# kachisys.net
KiCad netlist of a schematic drawn in EAGLE
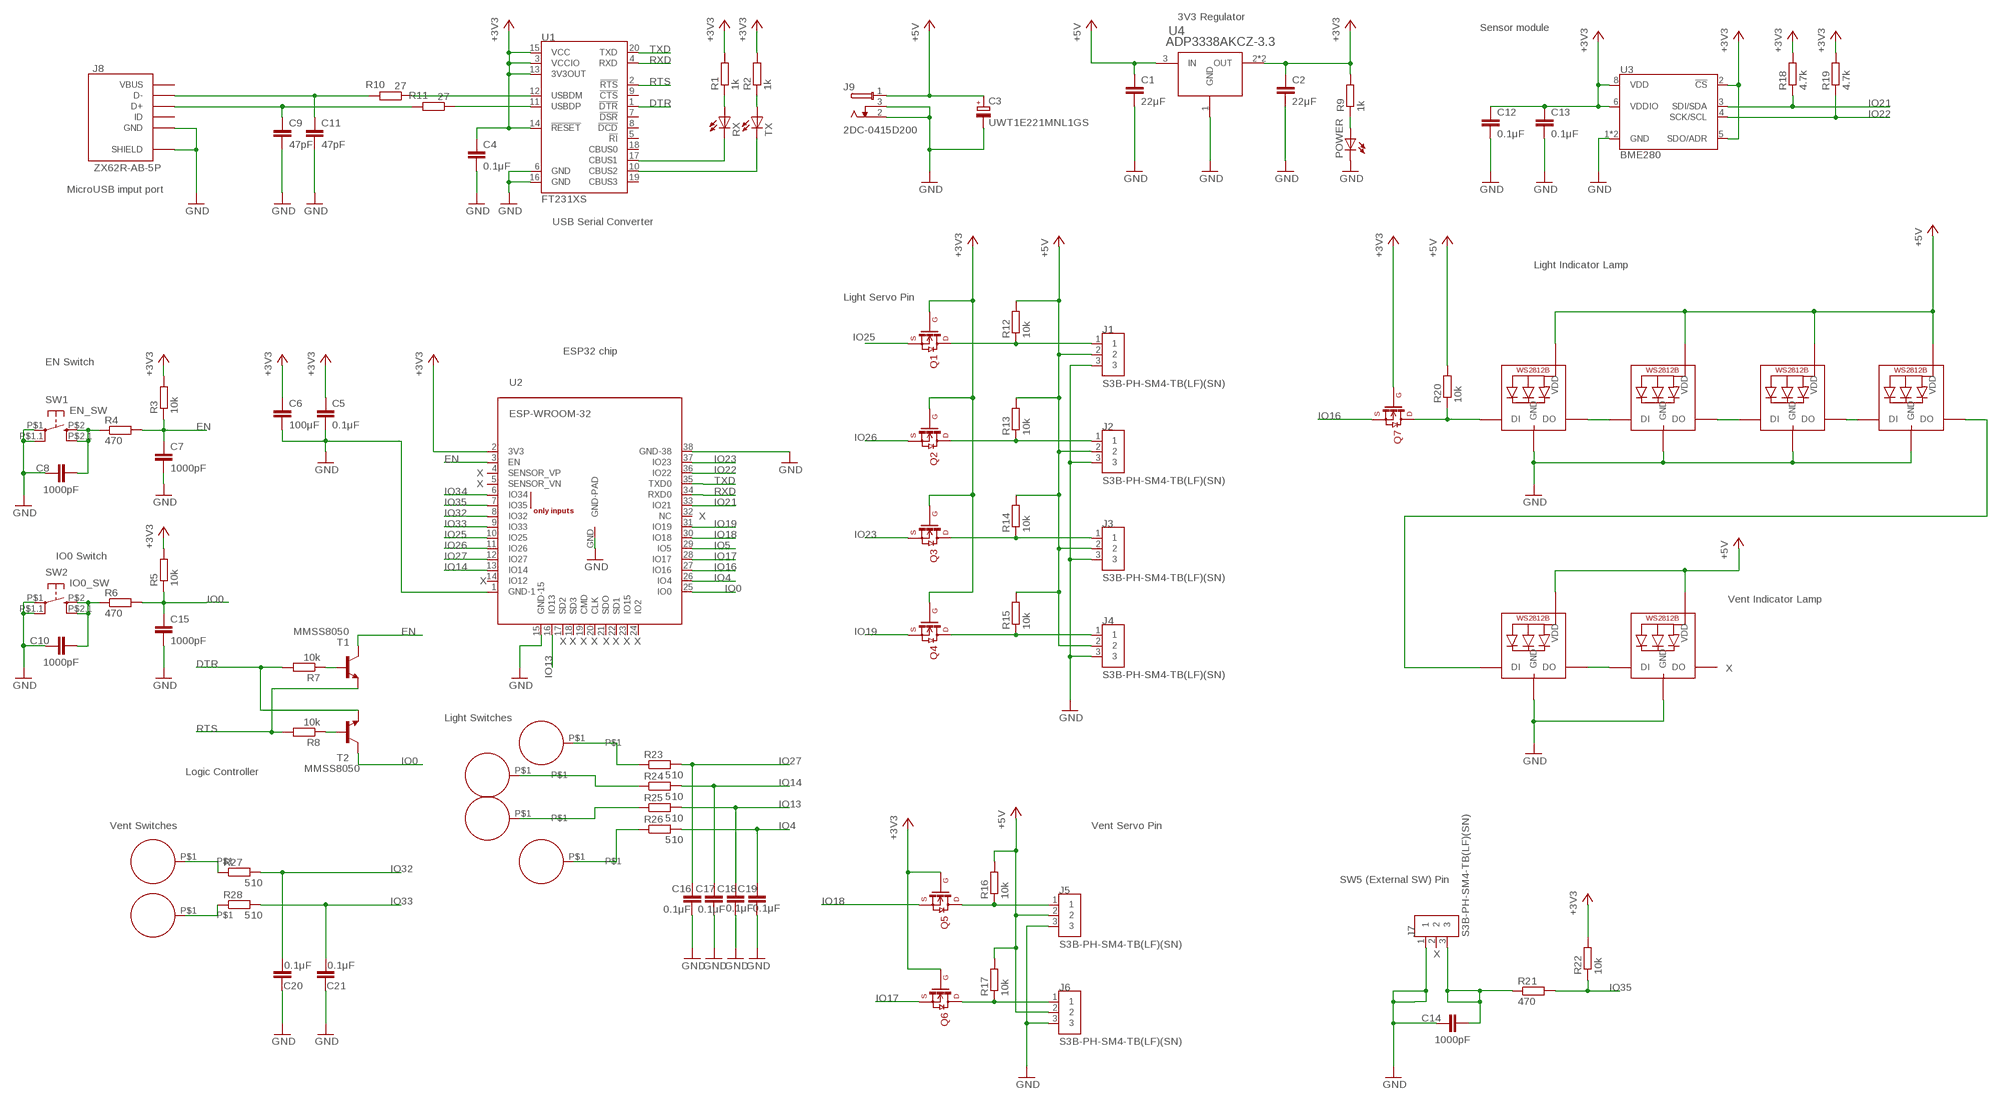
[diagram p0: schematic, sheet 1]

(export (version "E")
  (design (tool "Eeschema 10.0.6"))
  (components
    (comp (ref "C1")
      (value "22μF")
      (footprint "eagle-import:C2012")
      (libsource (lib "eagle-import") (part "resistor_348_C-EUC2012"))
    )
    (comp (ref "C2")
      (value "22μF")
      (footprint "eagle-import:C2012")
      (libsource (lib "eagle-import") (part "resistor_348_C-EUC2012"))
    )
    (comp (ref "C3")
      (value "UWT1E221MNL1GS")
      (footprint "eagle-import:NICHICON-ALMINUM-CAPACITOR-8MM")
      (libsource (lib "eagle-import") (part "UWT1E221MNL1GS"))
    )
    (comp (ref "C4")
      (value "0.1μF")
      (footprint "eagle-import:C0603")
      (libsource (lib "eagle-import") (part "resistor_348_C-EUC0603"))
    )
    (comp (ref "C5")
      (value "0.1μF")
      (footprint "eagle-import:C0603")
      (libsource (lib "eagle-import") (part "resistor_348_C-EUC0603"))
    )
    (comp (ref "C6")
      (value "100μF")
      (footprint "eagle-import:C3225")
      (libsource (lib "eagle-import") (part "resistor_348_C-EUC3225"))
    )
    (comp (ref "C7")
      (value "1000pF")
      (footprint "eagle-import:C0603")
      (libsource (lib "eagle-import") (part "resistor_348_C-EUC0603"))
    )
    (comp (ref "C8")
      (value "1000pF")
      (footprint "eagle-import:C0603")
      (libsource (lib "eagle-import") (part "resistor_348_C-EUC0603"))
    )
    (comp (ref "C9")
      (value "47pF")
      (footprint "eagle-import:C1608")
      (libsource (lib "eagle-import") (part "C-EUC1608"))
    )
    (comp (ref "C10")
      (value "1000pF")
      (footprint "eagle-import:C0603")
      (libsource (lib "eagle-import") (part "resistor_348_C-EUC0603"))
    )
    (comp (ref "C11")
      (value "47pF")
      (footprint "eagle-import:C1608")
      (libsource (lib "eagle-import") (part "C-EUC1608"))
    )
    (comp (ref "C12")
      (value "0.1μF")
      (footprint "eagle-import:C0603")
      (libsource (lib "eagle-import") (part "resistor_348_C-EUC0603"))
    )
    (comp (ref "C13")
      (value "0.1μF")
      (footprint "eagle-import:C0603")
      (libsource (lib "eagle-import") (part "resistor_348_C-EUC0603"))
    )
    (comp (ref "C14")
      (value "1000pF")
      (footprint "eagle-import:C0603")
      (libsource (lib "eagle-import") (part "resistor_348_C-EUC0603"))
    )
    (comp (ref "C15")
      (value "1000pF")
      (footprint "eagle-import:C0603")
      (libsource (lib "eagle-import") (part "resistor_348_C-EUC0603"))
    )
    (comp (ref "C16")
      (value "0.1μF")
      (footprint "eagle-import:C0603")
      (libsource (lib "eagle-import") (part "resistor_348_C-EUC0603"))
    )
    (comp (ref "C17")
      (value "0.1μF")
      (footprint "eagle-import:C0603")
      (libsource (lib "eagle-import") (part "resistor_348_C-EUC0603"))
    )
    (comp (ref "C18")
      (value "0.1μF")
      (footprint "eagle-import:C0603")
      (libsource (lib "eagle-import") (part "resistor_348_C-EUC0603"))
    )
    (comp (ref "C19")
      (value "0.1μF")
      (footprint "eagle-import:C0603")
      (libsource (lib "eagle-import") (part "resistor_348_C-EUC0603"))
    )
    (comp (ref "C20")
      (value "0.1μF")
      (footprint "eagle-import:C0603")
      (libsource (lib "eagle-import") (part "resistor_348_C-EUC0603"))
    )
    (comp (ref "C21")
      (value "0.1μF")
      (footprint "eagle-import:C0603")
      (libsource (lib "eagle-import") (part "resistor_348_C-EUC0603"))
    )
    (comp (ref "J1")
      (value "S3B-PH-SM4-TB(LF)(SN)")
      (footprint "eagle-import:JST_S3B-PH-SM4-TB(LF)(SN)")
      (fields
        (field (name "DIGI-KEY_PART_NUMBER") "455-1750-1-ND")
        (field (name "MF") "JST Sales")
        (field (name "MP") "S3B-PH-SM4-TB_LF__SN_")
      )
      (libsource (lib "eagle-import") (part "S3B-PH-SM4-TB(LF)(SN)"))
    )
    (comp (ref "J2")
      (value "S3B-PH-SM4-TB(LF)(SN)")
      (footprint "eagle-import:JST_S3B-PH-SM4-TB(LF)(SN)")
      (fields
        (field (name "DIGI-KEY_PART_NUMBER") "455-1750-1-ND")
        (field (name "MF") "JST Sales")
        (field (name "MP") "S3B-PH-SM4-TB_LF__SN_")
      )
      (libsource (lib "eagle-import") (part "S3B-PH-SM4-TB(LF)(SN)"))
    )
    (comp (ref "J3")
      (value "S3B-PH-SM4-TB(LF)(SN)")
      (footprint "eagle-import:JST_S3B-PH-SM4-TB(LF)(SN)")
      (fields
        (field (name "DIGI-KEY_PART_NUMBER") "455-1750-1-ND")
        (field (name "MF") "JST Sales")
        (field (name "MP") "S3B-PH-SM4-TB_LF__SN_")
      )
      (libsource (lib "eagle-import") (part "S3B-PH-SM4-TB(LF)(SN)"))
    )
    (comp (ref "J4")
      (value "S3B-PH-SM4-TB(LF)(SN)")
      (footprint "eagle-import:JST_S3B-PH-SM4-TB(LF)(SN)")
      (fields
        (field (name "DIGI-KEY_PART_NUMBER") "455-1750-1-ND")
        (field (name "MF") "JST Sales")
        (field (name "MP") "S3B-PH-SM4-TB_LF__SN_")
      )
      (libsource (lib "eagle-import") (part "S3B-PH-SM4-TB(LF)(SN)"))
    )
    (comp (ref "J5")
      (value "S3B-PH-SM4-TB(LF)(SN)")
      (footprint "eagle-import:JST_S3B-PH-SM4-TB(LF)(SN)")
      (fields
        (field (name "DIGI-KEY_PART_NUMBER") "455-1750-1-ND")
        (field (name "MF") "JST Sales")
        (field (name "MP") "S3B-PH-SM4-TB_LF__SN_")
      )
      (libsource (lib "eagle-import") (part "S3B-PH-SM4-TB(LF)(SN)"))
    )
    (comp (ref "J6")
      (value "S3B-PH-SM4-TB(LF)(SN)")
      (footprint "eagle-import:JST_S3B-PH-SM4-TB(LF)(SN)")
      (fields
        (field (name "DIGI-KEY_PART_NUMBER") "455-1750-1-ND")
        (field (name "MF") "JST Sales")
        (field (name "MP") "S3B-PH-SM4-TB_LF__SN_")
      )
      (libsource (lib "eagle-import") (part "S3B-PH-SM4-TB(LF)(SN)"))
    )
    (comp (ref "J7")
      (value "S3B-PH-SM4-TB(LF)(SN)")
      (footprint "eagle-import:JST_S3B-PH-SM4-TB(LF)(SN)")
      (fields
        (field (name "DIGI-KEY_PART_NUMBER") "455-1750-1-ND")
        (field (name "MF") "JST Sales")
        (field (name "MP") "S3B-PH-SM4-TB_LF__SN_")
      )
      (libsource (lib "eagle-import") (part "S3B-PH-SM4-TB(LF)(SN)"))
    )
    (comp (ref "J8")
      (value "ZX62R-AB-5P")
      (footprint "eagle-import:ZX62R-B-5PA")
      (libsource (lib "eagle-import") (part "ZX62R-AB-5P"))
    )
    (comp (ref "J9")
      (value "2DC-0415D200")
      (footprint "eagle-import:2DC-0415D200")
      (libsource (lib "eagle-import") (part "2DC-0415D200"))
    )
    (comp (ref "LED1")
      (value "WS2812B_5050N")
      (footprint "eagle-import:WS2812B-NARROW")
      (libsource (lib "eagle-import") (part "WS2812B_5050N"))
    )
    (comp (ref "LED2")
      (value "WS2812B_5050N")
      (footprint "eagle-import:WS2812B-NARROW")
      (libsource (lib "eagle-import") (part "WS2812B_5050N"))
    )
    (comp (ref "LED3")
      (value "WS2812B_5050N")
      (footprint "eagle-import:WS2812B-NARROW")
      (libsource (lib "eagle-import") (part "WS2812B_5050N"))
    )
    (comp (ref "LED4")
      (value "WS2812B_5050N")
      (footprint "eagle-import:WS2812B-NARROW")
      (libsource (lib "eagle-import") (part "WS2812B_5050N"))
    )
    (comp (ref "LED5")
      (value "WS2812B_5050N")
      (footprint "eagle-import:WS2812B-NARROW")
      (libsource (lib "eagle-import") (part "WS2812B_5050N"))
    )
    (comp (ref "LED6")
      (value "WS2812B_5050N")
      (footprint "eagle-import:WS2812B-NARROW")
      (libsource (lib "eagle-import") (part "WS2812B_5050N"))
    )
    (comp (ref "POWER")
      (value "LEDCHIP-LED0603")
      (footprint "eagle-import:CHIP-LED0603")
      (libsource (lib "eagle-import") (part "LEDCHIP-LED0603"))
    )
    (comp (ref "Q1")
      (value "BSS138")
      (footprint "eagle-import:SOT-23")
      (libsource (lib "eagle-import") (part "BSS138"))
    )
    (comp (ref "Q2")
      (value "BSS138")
      (footprint "eagle-import:SOT-23")
      (libsource (lib "eagle-import") (part "BSS138"))
    )
    (comp (ref "Q3")
      (value "BSS138")
      (footprint "eagle-import:SOT-23")
      (libsource (lib "eagle-import") (part "BSS138"))
    )
    (comp (ref "Q4")
      (value "BSS138")
      (footprint "eagle-import:SOT-23")
      (libsource (lib "eagle-import") (part "BSS138"))
    )
    (comp (ref "Q5")
      (value "BSS138")
      (footprint "eagle-import:SOT-23")
      (libsource (lib "eagle-import") (part "BSS138"))
    )
    (comp (ref "Q6")
      (value "BSS138")
      (footprint "eagle-import:SOT-23")
      (libsource (lib "eagle-import") (part "BSS138"))
    )
    (comp (ref "Q7")
      (value "BSS138")
      (footprint "eagle-import:SOT-23")
      (libsource (lib "eagle-import") (part "BSS138"))
    )
    (comp (ref "R1")
      (value "1k")
      (footprint "eagle-import:R0603")
      (libsource (lib "eagle-import") (part "R-EU_R0603"))
    )
    (comp (ref "R2")
      (value "1k")
      (footprint "eagle-import:R0603")
      (libsource (lib "eagle-import") (part "R-EU_R0603"))
    )
    (comp (ref "R3")
      (value "10k")
      (footprint "eagle-import:R0603")
      (libsource (lib "eagle-import") (part "R-EU_R0603"))
    )
    (comp (ref "R4")
      (value "470")
      (footprint "eagle-import:R0603")
      (libsource (lib "eagle-import") (part "R-EU_R0603"))
    )
    (comp (ref "R5")
      (value "10k")
      (footprint "eagle-import:R0603")
      (libsource (lib "eagle-import") (part "R-EU_R0603"))
    )
    (comp (ref "R6")
      (value "470")
      (footprint "eagle-import:R0603")
      (libsource (lib "eagle-import") (part "R-EU_R0603"))
    )
    (comp (ref "R7")
      (value "10k")
      (footprint "eagle-import:R0603")
      (libsource (lib "eagle-import") (part "R-EU_R0603"))
    )
    (comp (ref "R8")
      (value "10k")
      (footprint "eagle-import:R0603")
      (libsource (lib "eagle-import") (part "R-EU_R0603"))
    )
    (comp (ref "R9")
      (value "1k")
      (footprint "eagle-import:R0603")
      (libsource (lib "eagle-import") (part "R-EU_R0603"))
    )
    (comp (ref "R10")
      (value "27")
      (footprint "eagle-import:R0603")
      (libsource (lib "eagle-import") (part "R-EU_R0603"))
    )
    (comp (ref "R11")
      (value "27")
      (footprint "eagle-import:R0603")
      (libsource (lib "eagle-import") (part "R-EU_R0603"))
    )
    (comp (ref "R12")
      (value "10k")
      (footprint "eagle-import:R0603")
      (libsource (lib "eagle-import") (part "R-EU_R0603"))
    )
    (comp (ref "R13")
      (value "10k")
      (footprint "eagle-import:R0603")
      (libsource (lib "eagle-import") (part "R-EU_R0603"))
    )
    (comp (ref "R14")
      (value "10k")
      (footprint "eagle-import:R0603")
      (libsource (lib "eagle-import") (part "R-EU_R0603"))
    )
    (comp (ref "R15")
      (value "10k")
      (footprint "eagle-import:R0603")
      (libsource (lib "eagle-import") (part "R-EU_R0603"))
    )
    (comp (ref "R16")
      (value "10k")
      (footprint "eagle-import:R0603")
      (libsource (lib "eagle-import") (part "R-EU_R0603"))
    )
    (comp (ref "R17")
      (value "10k")
      (footprint "eagle-import:R0603")
      (libsource (lib "eagle-import") (part "R-EU_R0603"))
    )
    (comp (ref "R18")
      (value "4.7k")
      (footprint "eagle-import:R0603")
      (libsource (lib "eagle-import") (part "R-EU_R0603"))
    )
    (comp (ref "R19")
      (value "4.7k")
      (footprint "eagle-import:R0603")
      (libsource (lib "eagle-import") (part "R-EU_R0603"))
    )
    (comp (ref "R20")
      (value "10k")
      (footprint "eagle-import:R0603")
      (libsource (lib "eagle-import") (part "R-EU_R0603"))
    )
    (comp (ref "R21")
      (value "470")
      (footprint "eagle-import:R0603")
      (libsource (lib "eagle-import") (part "R-EU_R0603"))
    )
    (comp (ref "R22")
      (value "10k")
      (footprint "eagle-import:R0603")
      (libsource (lib "eagle-import") (part "R-EU_R0603"))
    )
    (comp (ref "R23")
      (value "510")
      (footprint "eagle-import:R0603")
      (libsource (lib "eagle-import") (part "R-EU_R0603"))
    )
    (comp (ref "R24")
      (value "510")
      (footprint "eagle-import:R0603")
      (libsource (lib "eagle-import") (part "R-EU_R0603"))
    )
    (comp (ref "R25")
      (value "510")
      (footprint "eagle-import:R0603")
      (libsource (lib "eagle-import") (part "R-EU_R0603"))
    )
    (comp (ref "R26")
      (value "510")
      (footprint "eagle-import:R0603")
      (libsource (lib "eagle-import") (part "R-EU_R0603"))
    )
    (comp (ref "R27")
      (value "510")
      (footprint "eagle-import:R0603")
      (libsource (lib "eagle-import") (part "R-EU_R0603"))
    )
    (comp (ref "R28")
      (value "510")
      (footprint "eagle-import:R0603")
      (libsource (lib "eagle-import") (part "R-EU_R0603"))
    )
    (comp (ref "RX")
      (value "LEDCHIP-LED0603")
      (footprint "eagle-import:CHIP-LED0603")
      (libsource (lib "eagle-import") (part "LEDCHIP-LED0603"))
    )
    (comp (ref "SW1")
      (value "EN_SW")
      (footprint "eagle-import:SKRPACE010")
      (libsource (lib "eagle-import") (part "DTS6_SMD"))
    )
    (comp (ref "SW2")
      (value "IO0_SW")
      (footprint "eagle-import:SKRPACE010")
      (libsource (lib "eagle-import") (part "DTS6_SMD"))
    )
    (comp (ref "T1")
      (value "MMSS8050")
      (footprint "eagle-import:SOT23-EBC")
      (libsource (lib "eagle-import") (part "-NPN-SOT23-EBC"))
    )
    (comp (ref "T2")
      (value "MMSS8050")
      (footprint "eagle-import:SOT23-EBC")
      (libsource (lib "eagle-import") (part "-NPN-SOT23-EBC"))
    )
    (comp (ref "TPAD1")
      (value "ESP32-TOUCHPAD")
      (footprint "eagle-import:ESP32-TOUCHPAD-10MM")
      (libsource (lib "eagle-import") (part "ESP32-TOUCHPAD"))
    )
    (comp (ref "TPAD2")
      (value "ESP32-TOUCHPAD")
      (footprint "eagle-import:ESP32-TOUCHPAD-10MM")
      (libsource (lib "eagle-import") (part "ESP32-TOUCHPAD"))
    )
    (comp (ref "TPAD3")
      (value "ESP32-TOUCHPAD")
      (footprint "eagle-import:ESP32-TOUCHPAD-10MM")
      (libsource (lib "eagle-import") (part "ESP32-TOUCHPAD"))
    )
    (comp (ref "TPAD4")
      (value "ESP32-TOUCHPAD")
      (footprint "eagle-import:ESP32-TOUCHPAD-10MM")
      (libsource (lib "eagle-import") (part "ESP32-TOUCHPAD"))
    )
    (comp (ref "TPAD5")
      (value "ESP32-TOUCHPAD")
      (footprint "eagle-import:ESP32-TOUCHPAD-10MM")
      (libsource (lib "eagle-import") (part "ESP32-TOUCHPAD"))
    )
    (comp (ref "TPAD6")
      (value "ESP32-TOUCHPAD")
      (footprint "eagle-import:ESP32-TOUCHPAD-10MM")
      (libsource (lib "eagle-import") (part "ESP32-TOUCHPAD"))
    )
    (comp (ref "TX")
      (value "LEDCHIP-LED0603")
      (footprint "eagle-import:CHIP-LED0603")
      (libsource (lib "eagle-import") (part "LEDCHIP-LED0603"))
    )
    (comp (ref "U1")
      (value "FT231XS")
      (footprint "eagle-import:SSOP20_L")
      (libsource (lib "eagle-import") (part "FT231XS"))
    )
    (comp (ref "U2")
      (value "ESP-WROOM-32")
      (footprint "eagle-import:ESP-WROOM-32")
      (libsource (lib "eagle-import") (part "ESP-WROOM-32"))
    )
    (comp (ref "U3")
      (value "BME280")
      (footprint "eagle-import:LGA-8-2.5X2.5")
      (libsource (lib "eagle-import") (part "BME280"))
    )
    (comp (ref "U4")
      (value "ADP3338AKCZ-3.3")
      (footprint "eagle-import:SOT233")
      (libsource (lib "eagle-import") (part "ADP3338AKCZ-3.3"))
    )
  )
  (nets
    (net (code "1") (name "+3V3") (class "Default")
      (node (ref "C12") (pin "1") (pinfunction "1_1") (pintype "passive"))
      (node (ref "C13") (pin "1") (pinfunction "1_1") (pintype "passive"))
      (node (ref "C2") (pin "1") (pinfunction "1_1") (pintype "passive"))
      (node (ref "C4") (pin "1") (pinfunction "1_1") (pintype "passive"))
      (node (ref "C5") (pin "1") (pinfunction "1_1") (pintype "passive"))
      (node (ref "C6") (pin "1") (pinfunction "1_1") (pintype "passive"))
      (node (ref "Q1") (pin "G") (pinfunction "G_G") (pintype "passive"))
      (node (ref "Q2") (pin "G") (pinfunction "G_G") (pintype "passive"))
      (node (ref "Q3") (pin "G") (pinfunction "G_G") (pintype "passive"))
      (node (ref "Q4") (pin "G") (pinfunction "G_G") (pintype "passive"))
      (node (ref "Q5") (pin "G") (pinfunction "G_G") (pintype "passive"))
      (node (ref "Q6") (pin "G") (pinfunction "G_G") (pintype "passive"))
      (node (ref "Q7") (pin "G") (pinfunction "G_G") (pintype "passive"))
      (node (ref "R1") (pin "2") (pinfunction "2_2") (pintype "passive"))
      (node (ref "R18") (pin "2") (pinfunction "2_2") (pintype "passive"))
      (node (ref "R19") (pin "2") (pinfunction "2_2") (pintype "passive"))
      (node (ref "R2") (pin "2") (pinfunction "2_2") (pintype "passive"))
      (node (ref "R22") (pin "2") (pinfunction "2_2") (pintype "passive"))
      (node (ref "R3") (pin "2") (pinfunction "2_2") (pintype "passive"))
      (node (ref "R5") (pin "2") (pinfunction "2_2") (pintype "passive"))
      (node (ref "R9") (pin "2") (pinfunction "2_2") (pintype "passive"))
      (node (ref "U1") (pin "13") (pinfunction "3V3OUT_13") (pintype "bidirectional"))
      (node (ref "U1") (pin "14") (pinfunction "~{RESET}_14") (pintype "bidirectional"))
      (node (ref "U1") (pin "15") (pinfunction "VCC_15") (pintype "bidirectional"))
      (node (ref "U1") (pin "3") (pinfunction "VCCIO_3") (pintype "bidirectional"))
      (node (ref "U2") (pin "2") (pinfunction "3V3_2") (pintype "bidirectional"))
      (node (ref "U3") (pin "2") (pinfunction "~{CS}_2") (pintype "bidirectional"))
      (node (ref "U3") (pin "5") (pinfunction "SDO/ADR_5") (pintype "bidirectional"))
      (node (ref "U3") (pin "6") (pinfunction "VDDIO_6") (pintype "bidirectional"))
      (node (ref "U3") (pin "8") (pinfunction "VDD_8") (pintype "bidirectional"))
      (node (ref "U4") (pin "2") (pinfunction "OUT_2") (pintype "passive"))
      (node (ref "U4") (pin "4") (pinfunction "OUT_4") (pintype "passive"))
    )
    (net (code "2") (name "+5V") (class "Default")
      (node (ref "C1") (pin "1") (pinfunction "1_1") (pintype "passive"))
      (node (ref "C3") (pin "POS") (pinfunction "+_POS") (pintype "passive"))
      (node (ref "J1") (pin "2") (pinfunction "2_2") (pintype "passive"))
      (node (ref "J2") (pin "2") (pinfunction "2_2") (pintype "passive"))
      (node (ref "J3") (pin "2") (pinfunction "2_2") (pintype "passive"))
      (node (ref "J4") (pin "2") (pinfunction "2_2") (pintype "passive"))
      (node (ref "J5") (pin "2") (pinfunction "2_2") (pintype "passive"))
      (node (ref "J6") (pin "2") (pinfunction "2_2") (pintype "passive"))
      (node (ref "J9") (pin "1") (pinfunction "1_1") (pintype "passive"))
      (node (ref "LED1") (pin "1-VDD") (pinfunction "VDD_1-VDD") (pintype "power_in"))
      (node (ref "LED2") (pin "1-VDD") (pinfunction "VDD_1-VDD") (pintype "power_in"))
      (node (ref "LED3") (pin "1-VDD") (pinfunction "VDD_1-VDD") (pintype "power_in"))
      (node (ref "LED4") (pin "1-VDD") (pinfunction "VDD_1-VDD") (pintype "power_in"))
      (node (ref "LED5") (pin "1-VDD") (pinfunction "VDD_1-VDD") (pintype "power_in"))
      (node (ref "LED6") (pin "1-VDD") (pinfunction "VDD_1-VDD") (pintype "power_in"))
      (node (ref "R12") (pin "2") (pinfunction "2_2") (pintype "passive"))
      (node (ref "R13") (pin "2") (pinfunction "2_2") (pintype "passive"))
      (node (ref "R14") (pin "2") (pinfunction "2_2") (pintype "passive"))
      (node (ref "R15") (pin "2") (pinfunction "2_2") (pintype "passive"))
      (node (ref "R16") (pin "2") (pinfunction "2_2") (pintype "passive"))
      (node (ref "R17") (pin "2") (pinfunction "2_2") (pintype "passive"))
      (node (ref "R20") (pin "2") (pinfunction "2_2") (pintype "passive"))
      (node (ref "U4") (pin "3") (pinfunction "IN_3") (pintype "passive"))
    )
    (net (code "3") (name "/DTR") (class "Default")
      (node (ref "R7") (pin "2") (pinfunction "2_2") (pintype "passive"))
      (node (ref "T2") (pin "E") (pinfunction "E_E") (pintype "passive"))
      (node (ref "U1") (pin "1") (pinfunction "~{DTR}_1") (pintype "bidirectional"))
    )
    (net (code "4") (name "/EN") (class "Default")
      (node (ref "C7") (pin "1") (pinfunction "1_1") (pintype "passive"))
      (node (ref "R3") (pin "1") (pinfunction "1_1") (pintype "passive"))
      (node (ref "R4") (pin "2") (pinfunction "2_2") (pintype "passive"))
      (node (ref "T1") (pin "C") (pinfunction "C_C") (pintype "passive"))
      (node (ref "U2") (pin "3") (pinfunction "EN_3") (pintype "bidirectional"))
    )
    (net (code "5") (name "/IO0") (class "Default")
      (node (ref "C15") (pin "1") (pinfunction "1_1") (pintype "passive"))
      (node (ref "R5") (pin "1") (pinfunction "1_1") (pintype "passive"))
      (node (ref "R6") (pin "2") (pinfunction "2_2") (pintype "passive"))
      (node (ref "T2") (pin "C") (pinfunction "C_C") (pintype "passive"))
      (node (ref "U2") (pin "25") (pinfunction "IO0_25") (pintype "bidirectional"))
    )
    (net (code "6") (name "/IO4") (class "Default")
      (node (ref "C19") (pin "1") (pinfunction "1_1") (pintype "passive"))
      (node (ref "R26") (pin "2") (pinfunction "2_2") (pintype "passive"))
      (node (ref "U2") (pin "26") (pinfunction "IO4_26") (pintype "bidirectional"))
    )
    (net (code "7") (name "/IO5") (class "Default")
      (node (ref "U2") (pin "29") (pinfunction "IO5_29") (pintype "bidirectional"))
    )
    (net (code "8") (name "/IO13") (class "Default")
      (node (ref "C18") (pin "1") (pinfunction "1_1") (pintype "passive"))
      (node (ref "R25") (pin "2") (pinfunction "2_2") (pintype "passive"))
      (node (ref "U2") (pin "16") (pinfunction "IO13_16") (pintype "bidirectional"))
    )
    (net (code "9") (name "/IO14") (class "Default")
      (node (ref "C17") (pin "1") (pinfunction "1_1") (pintype "passive"))
      (node (ref "R24") (pin "2") (pinfunction "2_2") (pintype "passive"))
      (node (ref "U2") (pin "13") (pinfunction "IO14_13") (pintype "bidirectional"))
    )
    (net (code "10") (name "/IO16") (class "Default")
      (node (ref "Q7") (pin "S") (pinfunction "S_S") (pintype "passive"))
      (node (ref "U2") (pin "27") (pinfunction "IO16_27") (pintype "bidirectional"))
    )
    (net (code "11") (name "/IO17") (class "Default")
      (node (ref "Q6") (pin "S") (pinfunction "S_S") (pintype "passive"))
      (node (ref "U2") (pin "28") (pinfunction "IO17_28") (pintype "bidirectional"))
    )
    (net (code "12") (name "/IO18") (class "Default")
      (node (ref "Q5") (pin "S") (pinfunction "S_S") (pintype "passive"))
      (node (ref "U2") (pin "30") (pinfunction "IO18_30") (pintype "bidirectional"))
    )
    (net (code "13") (name "/IO19") (class "Default")
      (node (ref "Q4") (pin "S") (pinfunction "S_S") (pintype "passive"))
      (node (ref "U2") (pin "31") (pinfunction "IO19_31") (pintype "bidirectional"))
    )
    (net (code "14") (name "/IO21") (class "Default")
      (node (ref "R18") (pin "1") (pinfunction "1_1") (pintype "passive"))
      (node (ref "U2") (pin "33") (pinfunction "IO21_33") (pintype "bidirectional"))
      (node (ref "U3") (pin "3") (pinfunction "SDI/SDA_3") (pintype "bidirectional"))
    )
    (net (code "15") (name "/IO22") (class "Default")
      (node (ref "R19") (pin "1") (pinfunction "1_1") (pintype "passive"))
      (node (ref "U2") (pin "36") (pinfunction "IO22_36") (pintype "bidirectional"))
      (node (ref "U3") (pin "4") (pinfunction "SCK/SCL_4") (pintype "bidirectional"))
    )
    (net (code "16") (name "/IO23") (class "Default")
      (node (ref "Q3") (pin "S") (pinfunction "S_S") (pintype "passive"))
      (node (ref "U2") (pin "37") (pinfunction "IO23_37") (pintype "bidirectional"))
    )
    (net (code "17") (name "/IO25") (class "Default")
      (node (ref "Q1") (pin "S") (pinfunction "S_S") (pintype "passive"))
      (node (ref "U2") (pin "10") (pinfunction "IO25_10") (pintype "bidirectional"))
    )
    (net (code "18") (name "/IO26") (class "Default")
      (node (ref "Q2") (pin "S") (pinfunction "S_S") (pintype "passive"))
      (node (ref "U2") (pin "11") (pinfunction "IO26_11") (pintype "bidirectional"))
    )
    (net (code "19") (name "/IO27") (class "Default")
      (node (ref "C16") (pin "1") (pinfunction "1_1") (pintype "passive"))
      (node (ref "R23") (pin "2") (pinfunction "2_2") (pintype "passive"))
      (node (ref "U2") (pin "12") (pinfunction "IO27_12") (pintype "bidirectional"))
    )
    (net (code "20") (name "/IO32") (class "Default")
      (node (ref "C20") (pin "2") (pinfunction "2_2") (pintype "passive"))
      (node (ref "R27") (pin "2") (pinfunction "2_2") (pintype "passive"))
      (node (ref "U2") (pin "8") (pinfunction "IO32_8") (pintype "bidirectional"))
    )
    (net (code "21") (name "/IO33") (class "Default")
      (node (ref "C21") (pin "2") (pinfunction "2_2") (pintype "passive"))
      (node (ref "R28") (pin "2") (pinfunction "2_2") (pintype "passive"))
      (node (ref "U2") (pin "9") (pinfunction "IO33_9") (pintype "bidirectional"))
    )
    (net (code "22") (name "/IO34") (class "Default")
      (node (ref "U2") (pin "6") (pinfunction "IO34_6") (pintype "input"))
    )
    (net (code "23") (name "/IO35") (class "Default")
      (node (ref "R21") (pin "2") (pinfunction "2_2") (pintype "passive"))
      (node (ref "R22") (pin "1") (pinfunction "1_1") (pintype "passive"))
      (node (ref "U2") (pin "7") (pinfunction "IO35_7") (pintype "input"))
    )
    (net (code "24") (name "/RTS") (class "Default")
      (node (ref "R8") (pin "2") (pinfunction "2_2") (pintype "passive"))
      (node (ref "T1") (pin "E") (pinfunction "E_E") (pintype "passive"))
      (node (ref "U1") (pin "2") (pinfunction "~{RTS}_2") (pintype "bidirectional"))
    )
    (net (code "25") (name "/RXD") (class "Default")
      (node (ref "U1") (pin "4") (pinfunction "RXD_4") (pintype "bidirectional"))
      (node (ref "U2") (pin "34") (pinfunction "RXD0_34") (pintype "bidirectional"))
    )
    (net (code "26") (name "/TXD") (class "Default")
      (node (ref "U1") (pin "20") (pinfunction "TXD_20") (pintype "bidirectional"))
      (node (ref "U2") (pin "35") (pinfunction "TXD0_35") (pintype "bidirectional"))
    )
    (net (code "27") (name "GND") (class "Default")
      (node (ref "C1") (pin "2") (pinfunction "2_2") (pintype "passive"))
      (node (ref "C10") (pin "1") (pinfunction "1_1") (pintype "passive"))
      (node (ref "C11") (pin "2") (pinfunction "2_2") (pintype "passive"))
      (node (ref "C12") (pin "2") (pinfunction "2_2") (pintype "passive"))
      (node (ref "C13") (pin "2") (pinfunction "2_2") (pintype "passive"))
      (node (ref "C14") (pin "1") (pinfunction "1_1") (pintype "passive"))
      (node (ref "C15") (pin "2") (pinfunction "2_2") (pintype "passive"))
      (node (ref "C16") (pin "2") (pinfunction "2_2") (pintype "passive"))
      (node (ref "C17") (pin "2") (pinfunction "2_2") (pintype "passive"))
      (node (ref "C18") (pin "2") (pinfunction "2_2") (pintype "passive"))
      (node (ref "C19") (pin "2") (pinfunction "2_2") (pintype "passive"))
      (node (ref "C2") (pin "2") (pinfunction "2_2") (pintype "passive"))
      (node (ref "C20") (pin "1") (pinfunction "1_1") (pintype "passive"))
      (node (ref "C21") (pin "1") (pinfunction "1_1") (pintype "passive"))
      (node (ref "C3") (pin "NEG") (pinfunction "-_NEG") (pintype "passive"))
      (node (ref "C4") (pin "2") (pinfunction "2_2") (pintype "passive"))
      (node (ref "C5") (pin "2") (pinfunction "2_2") (pintype "passive"))
      (node (ref "C6") (pin "2") (pinfunction "2_2") (pintype "passive"))
      (node (ref "C7") (pin "2") (pinfunction "2_2") (pintype "passive"))
      (node (ref "C8") (pin "1") (pinfunction "1_1") (pintype "passive"))
      (node (ref "C9") (pin "2") (pinfunction "2_2") (pintype "passive"))
      (node (ref "J1") (pin "3") (pinfunction "3_3") (pintype "passive"))
      (node (ref "J2") (pin "3") (pinfunction "3_3") (pintype "passive"))
      (node (ref "J3") (pin "3") (pinfunction "3_3") (pintype "passive"))
      (node (ref "J4") (pin "3") (pinfunction "3_3") (pintype "passive"))
      (node (ref "J5") (pin "3") (pinfunction "3_3") (pintype "passive"))
      (node (ref "J6") (pin "3") (pinfunction "3_3") (pintype "passive"))
      (node (ref "J7") (pin "1") (pinfunction "1_1") (pintype "passive"))
      (node (ref "J8") (pin "GND") (pinfunction "GND_GND") (pintype "bidirectional"))
      (node (ref "J8") (pin "SHIELD@1") (pinfunction "SHIELD_SHIELD@1") (pintype "bidirectional"))
      (node (ref "J8") (pin "SHIELD@2") (pinfunction "SHIELD_SHIELD@2") (pintype "bidirectional"))
      (node (ref "J8") (pin "SHIELD@3") (pinfunction "SHIELD_SHIELD@3") (pintype "bidirectional"))
      (node (ref "J8") (pin "SHIELD@4") (pinfunction "SHIELD_SHIELD@4") (pintype "bidirectional"))
      (node (ref "J9") (pin "2") (pinfunction "2_2") (pintype "passive"))
      (node (ref "J9") (pin "3") (pinfunction "3_3") (pintype "passive"))
      (node (ref "LED1") (pin "3-GND") (pinfunction "GND_3-GND") (pintype "power_in"))
      (node (ref "LED2") (pin "3-GND") (pinfunction "GND_3-GND") (pintype "power_in"))
      (node (ref "LED3") (pin "3-GND") (pinfunction "GND_3-GND") (pintype "power_in"))
      (node (ref "LED4") (pin "3-GND") (pinfunction "GND_3-GND") (pintype "power_in"))
      (node (ref "LED5") (pin "3-GND") (pinfunction "GND_3-GND") (pintype "power_in"))
      (node (ref "LED6") (pin "3-GND") (pinfunction "GND_3-GND") (pintype "power_in"))
      (node (ref "POWER") (pin "C") (pinfunction "C_C") (pintype "passive"))
      (node (ref "SW1") (pin "P$1") (pinfunction "P_P$1") (pintype "passive"))
      (node (ref "SW1") (pin "P$1.1") (pinfunction "P1_P$1.1") (pintype "passive"))
      (node (ref "SW2") (pin "P$1") (pinfunction "P_P$1") (pintype "passive"))
      (node (ref "SW2") (pin "P$1.1") (pinfunction "P1_P$1.1") (pintype "passive"))
      (node (ref "U1") (pin "16") (pinfunction "GND_16") (pintype "bidirectional"))
      (node (ref "U1") (pin "6") (pinfunction "GND_6") (pintype "bidirectional"))
      (node (ref "U2") (pin "1") (pinfunction "GND-1_1") (pintype "bidirectional"))
      (node (ref "U2") (pin "15") (pinfunction "GND-15_15") (pintype "bidirectional"))
      (node (ref "U2") (pin "38") (pinfunction "GND-38_38") (pintype "bidirectional"))
      (node (ref "U2") (pin "GND") (pinfunction "GND-PAD_GND") (pintype "bidirectional"))
      (node (ref "U3") (pin "1") (pinfunction "GND_1") (pintype "bidirectional"))
      (node (ref "U3") (pin "7") (pinfunction "GND_7") (pintype "bidirectional"))
      (node (ref "U4") (pin "1") (pinfunction "GND_1") (pintype "passive"))
    )
    (net (code "28") (name "Net-(C9-Pad1)") (class "Default")
      (node (ref "C9") (pin "1") (pinfunction "1_1") (pintype "passive"))
      (node (ref "J8") (pin "D+") (pinfunction "D+_D+") (pintype "bidirectional"))
      (node (ref "R11") (pin "2") (pinfunction "2_2") (pintype "passive"))
    )
    (net (code "29") (name "Net-(C11-Pad1)") (class "Default")
      (node (ref "C11") (pin "1") (pinfunction "1_1") (pintype "passive"))
      (node (ref "J8") (pin "D-") (pinfunction "D-_D-") (pintype "bidirectional"))
      (node (ref "R10") (pin "2") (pinfunction "2_2") (pintype "passive"))
    )
    (net (code "30") (name "Net-(C14-Pad2)") (class "Default")
      (node (ref "C14") (pin "2") (pinfunction "2_2") (pintype "passive"))
      (node (ref "J7") (pin "3") (pinfunction "3_3") (pintype "passive"))
      (node (ref "R21") (pin "1") (pinfunction "1_1") (pintype "passive"))
    )
    (net (code "31") (name "Net-(J1-Pad1)") (class "Default")
      (node (ref "J1") (pin "1") (pinfunction "1_1") (pintype "passive"))
      (node (ref "Q1") (pin "D") (pinfunction "D_D") (pintype "passive"))
      (node (ref "R12") (pin "1") (pinfunction "1_1") (pintype "passive"))
    )
    (net (code "32") (name "Net-(J2-Pad1)") (class "Default")
      (node (ref "J2") (pin "1") (pinfunction "1_1") (pintype "passive"))
      (node (ref "Q2") (pin "D") (pinfunction "D_D") (pintype "passive"))
      (node (ref "R13") (pin "1") (pinfunction "1_1") (pintype "passive"))
    )
    (net (code "33") (name "Net-(J3-Pad1)") (class "Default")
      (node (ref "J3") (pin "1") (pinfunction "1_1") (pintype "passive"))
      (node (ref "Q3") (pin "D") (pinfunction "D_D") (pintype "passive"))
      (node (ref "R14") (pin "1") (pinfunction "1_1") (pintype "passive"))
    )
    (net (code "34") (name "Net-(J4-Pad1)") (class "Default")
      (node (ref "J4") (pin "1") (pinfunction "1_1") (pintype "passive"))
      (node (ref "Q4") (pin "D") (pinfunction "D_D") (pintype "passive"))
      (node (ref "R15") (pin "1") (pinfunction "1_1") (pintype "passive"))
    )
    (net (code "35") (name "Net-(J5-Pad1)") (class "Default")
      (node (ref "J5") (pin "1") (pinfunction "1_1") (pintype "passive"))
      (node (ref "Q5") (pin "D") (pinfunction "D_D") (pintype "passive"))
      (node (ref "R16") (pin "1") (pinfunction "1_1") (pintype "passive"))
    )
    (net (code "36") (name "Net-(J6-Pad1)") (class "Default")
      (node (ref "J6") (pin "1") (pinfunction "1_1") (pintype "passive"))
      (node (ref "Q6") (pin "D") (pinfunction "D_D") (pintype "passive"))
      (node (ref "R17") (pin "1") (pinfunction "1_1") (pintype "passive"))
    )
    (net (code "37") (name "Net-(LED1-DI)") (class "Default")
      (node (ref "LED1") (pin "4-DIN") (pinfunction "DI_4-DIN") (pintype "input"))
      (node (ref "Q7") (pin "D") (pinfunction "D_D") (pintype "passive"))
      (node (ref "R20") (pin "1") (pinfunction "1_1") (pintype "passive"))
    )
    (net (code "38") (name "Net-(LED1-DO)") (class "Default")
      (node (ref "LED1") (pin "2-DOUT") (pinfunction "DO_2-DOUT") (pintype "output"))
      (node (ref "LED2") (pin "4-DIN") (pinfunction "DI_4-DIN") (pintype "input"))
    )
    (net (code "39") (name "Net-(LED2-DO)") (class "Default")
      (node (ref "LED2") (pin "2-DOUT") (pinfunction "DO_2-DOUT") (pintype "output"))
      (node (ref "LED3") (pin "4-DIN") (pinfunction "DI_4-DIN") (pintype "input"))
    )
    (net (code "40") (name "Net-(LED3-DO)") (class "Default")
      (node (ref "LED3") (pin "2-DOUT") (pinfunction "DO_2-DOUT") (pintype "output"))
      (node (ref "LED4") (pin "4-DIN") (pinfunction "DI_4-DIN") (pintype "input"))
    )
    (net (code "41") (name "Net-(LED4-DO)") (class "Default")
      (node (ref "LED4") (pin "2-DOUT") (pinfunction "DO_2-DOUT") (pintype "output"))
      (node (ref "LED5") (pin "4-DIN") (pinfunction "DI_4-DIN") (pintype "input"))
    )
    (net (code "42") (name "Net-(LED5-DO)") (class "Default")
      (node (ref "LED5") (pin "2-DOUT") (pinfunction "DO_2-DOUT") (pintype "output"))
      (node (ref "LED6") (pin "4-DIN") (pinfunction "DI_4-DIN") (pintype "input"))
    )
    (net (code "43") (name "Net-(POWER-PadA)") (class "Default")
      (node (ref "POWER") (pin "A") (pinfunction "A_A") (pintype "passive"))
      (node (ref "R9") (pin "1") (pinfunction "1_1") (pintype "passive"))
    )
    (net (code "44") (name "Net-(R1-Pad1)") (class "Default")
      (node (ref "R1") (pin "1") (pinfunction "1_1") (pintype "passive"))
      (node (ref "RX") (pin "A") (pinfunction "A_A") (pintype "passive"))
    )
    (net (code "45") (name "Net-(R2-Pad1)") (class "Default")
      (node (ref "R2") (pin "1") (pinfunction "1_1") (pintype "passive"))
      (node (ref "TX") (pin "A") (pinfunction "A_A") (pintype "passive"))
    )
    (net (code "46") (name "Net-(R7-Pad1)") (class "Default")
      (node (ref "R7") (pin "1") (pinfunction "1_1") (pintype "passive"))
      (node (ref "T1") (pin "B") (pinfunction "B_B") (pintype "passive"))
    )
    (net (code "47") (name "Net-(R8-Pad1)") (class "Default")
      (node (ref "R8") (pin "1") (pinfunction "1_1") (pintype "passive"))
      (node (ref "T2") (pin "B") (pinfunction "B_B") (pintype "passive"))
    )
    (net (code "48") (name "Net-(R23-Pad1)") (class "Default")
      (node (ref "R23") (pin "1") (pinfunction "1_1") (pintype "passive"))
      (node (ref "TPAD1") (pin "P$1") (pinfunction "P$1_P$1") (pintype "bidirectional"))
    )
    (net (code "49") (name "Net-(R24-Pad1)") (class "Default")
      (node (ref "R24") (pin "1") (pinfunction "1_1") (pintype "passive"))
      (node (ref "TPAD2") (pin "P$1") (pinfunction "P$1_P$1") (pintype "bidirectional"))
    )
    (net (code "50") (name "Net-(R25-Pad1)") (class "Default")
      (node (ref "R25") (pin "1") (pinfunction "1_1") (pintype "passive"))
      (node (ref "TPAD3") (pin "P$1") (pinfunction "P$1_P$1") (pintype "bidirectional"))
    )
    (net (code "51") (name "Net-(R26-Pad1)") (class "Default")
      (node (ref "R26") (pin "1") (pinfunction "1_1") (pintype "passive"))
      (node (ref "TPAD4") (pin "P$1") (pinfunction "P$1_P$1") (pintype "bidirectional"))
    )
    (net (code "52") (name "Net-(R27-Pad1)") (class "Default")
      (node (ref "R27") (pin "1") (pinfunction "1_1") (pintype "passive"))
      (node (ref "TPAD5") (pin "P$1") (pinfunction "P$1_P$1") (pintype "bidirectional"))
    )
    (net (code "53") (name "Net-(R28-Pad1)") (class "Default")
      (node (ref "R28") (pin "1") (pinfunction "1_1") (pintype "passive"))
      (node (ref "TPAD6") (pin "P$1") (pinfunction "P$1_P$1") (pintype "bidirectional"))
    )
    (net (code "54") (name "Net-(SW1-S)") (class "Default")
      (node (ref "C8") (pin "2") (pinfunction "2_2") (pintype "passive"))
      (node (ref "R4") (pin "1") (pinfunction "1_1") (pintype "passive"))
      (node (ref "SW1") (pin "P$2") (pinfunction "S_P$2") (pintype "passive"))
      (node (ref "SW1") (pin "P$2.1") (pinfunction "S1_P$2.1") (pintype "passive"))
    )
    (net (code "55") (name "Net-(SW2-S)") (class "Default")
      (node (ref "C10") (pin "2") (pinfunction "2_2") (pintype "passive"))
      (node (ref "R6") (pin "1") (pinfunction "1_1") (pintype "passive"))
      (node (ref "SW2") (pin "P$2") (pinfunction "S_P$2") (pintype "passive"))
      (node (ref "SW2") (pin "P$2.1") (pinfunction "S1_P$2.1") (pintype "passive"))
    )
    (net (code "56") (name "Net-(U1-CBUS1)") (class "Default")
      (node (ref "RX") (pin "C") (pinfunction "C_C") (pintype "passive"))
      (node (ref "U1") (pin "17") (pinfunction "CBUS1_17") (pintype "bidirectional"))
    )
    (net (code "57") (name "Net-(U1-CBUS2)") (class "Default")
      (node (ref "TX") (pin "C") (pinfunction "C_C") (pintype "passive"))
      (node (ref "U1") (pin "10") (pinfunction "CBUS2_10") (pintype "bidirectional"))
    )
    (net (code "58") (name "Net-(U1-USBDM)") (class "Default")
      (node (ref "R10") (pin "1") (pinfunction "1_1") (pintype "passive"))
      (node (ref "U1") (pin "12") (pinfunction "USBDM_12") (pintype "bidirectional"))
    )
    (net (code "59") (name "Net-(U1-USBDP)") (class "Default")
      (node (ref "R11") (pin "1") (pinfunction "1_1") (pintype "passive"))
      (node (ref "U1") (pin "11") (pinfunction "USBDP_11") (pintype "bidirectional"))
    )
    (net (code "60") (name "unconnected-(J7-Pad2)") (class "Default")
      (node (ref "J7") (pin "2") (pinfunction "2_2") (pintype "passive"))
    )
    (net (code "61") (name "unconnected-(J8-PadID)") (class "Default")
      (node (ref "J8") (pin "ID") (pinfunction "ID_ID") (pintype "bidirectional"))
    )
    (net (code "62") (name "unconnected-(J8-VBUS-PadVCC)") (class "Default")
      (node (ref "J8") (pin "VCC") (pinfunction "VBUS_VCC") (pintype "bidirectional"))
    )
    (net (code "63") (name "unconnected-(LED6-DO-Pad2-DOUT)") (class "Default")
      (node (ref "LED6") (pin "2-DOUT") (pinfunction "DO_2-DOUT") (pintype "output"))
    )
    (net (code "64") (name "unconnected-(U1-CBUS0-Pad18)") (class "Default")
      (node (ref "U1") (pin "18") (pinfunction "CBUS0_18") (pintype "bidirectional"))
    )
    (net (code "65") (name "unconnected-(U1-CBUS3-Pad19)") (class "Default")
      (node (ref "U1") (pin "19") (pinfunction "CBUS3_19") (pintype "bidirectional"))
    )
    (net (code "66") (name "unconnected-(U1-~{CTS}-Pad9)") (class "Default")
      (node (ref "U1") (pin "9") (pinfunction "~{CTS}_9") (pintype "bidirectional"))
    )
    (net (code "67") (name "unconnected-(U1-~{DCD}-Pad8)") (class "Default")
      (node (ref "U1") (pin "8") (pinfunction "~{DCD}_8") (pintype "bidirectional"))
    )
    (net (code "68") (name "unconnected-(U1-~{DSR}-Pad7)") (class "Default")
      (node (ref "U1") (pin "7") (pinfunction "~{DSR}_7") (pintype "bidirectional"))
    )
    (net (code "69") (name "unconnected-(U1-~{RI}-Pad5)") (class "Default")
      (node (ref "U1") (pin "5") (pinfunction "~{RI}_5") (pintype "bidirectional"))
    )
    (net (code "70") (name "unconnected-(U2-CLK-Pad20)") (class "Default")
      (node (ref "U2") (pin "20") (pinfunction "CLK_20") (pintype "bidirectional"))
    )
    (net (code "71") (name "unconnected-(U2-CMD-Pad19)") (class "Default")
      (node (ref "U2") (pin "19") (pinfunction "CMD_19") (pintype "bidirectional"))
    )
    (net (code "72") (name "unconnected-(U2-IO2-Pad24)") (class "Default")
      (node (ref "U2") (pin "24") (pinfunction "IO2_24") (pintype "bidirectional"))
    )
    (net (code "73") (name "unconnected-(U2-IO12-Pad14)") (class "Default")
      (node (ref "U2") (pin "14") (pinfunction "IO12_14") (pintype "bidirectional"))
    )
    (net (code "74") (name "unconnected-(U2-IO15-Pad23)") (class "Default")
      (node (ref "U2") (pin "23") (pinfunction "IO15_23") (pintype "bidirectional"))
    )
    (net (code "75") (name "unconnected-(U2-NC-Pad32)") (class "Default")
      (node (ref "U2") (pin "32") (pinfunction "NC_32") (pintype "bidirectional"))
    )
    (net (code "76") (name "unconnected-(U2-SD1-Pad22)") (class "Default")
      (node (ref "U2") (pin "22") (pinfunction "SD1_22") (pintype "bidirectional"))
    )
    (net (code "77") (name "unconnected-(U2-SD2-Pad17)") (class "Default")
      (node (ref "U2") (pin "17") (pinfunction "SD2_17") (pintype "bidirectional"))
    )
    (net (code "78") (name "unconnected-(U2-SD3-Pad18)") (class "Default")
      (node (ref "U2") (pin "18") (pinfunction "SD3_18") (pintype "bidirectional"))
    )
    (net (code "79") (name "unconnected-(U2-SDO-Pad21)") (class "Default")
      (node (ref "U2") (pin "21") (pinfunction "SDO_21") (pintype "bidirectional"))
    )
    (net (code "80") (name "unconnected-(U2-SENSOR_VN-Pad5)") (class "Default")
      (node (ref "U2") (pin "5") (pinfunction "SENSOR_VN_5") (pintype "input"))
    )
    (net (code "81") (name "unconnected-(U2-SENSOR_VP-Pad4)") (class "Default")
      (node (ref "U2") (pin "4") (pinfunction "SENSOR_VP_4") (pintype "input"))
    )
  )
)
